# Main.net
KiCad netlist of a schematic drawn in Altium Designer
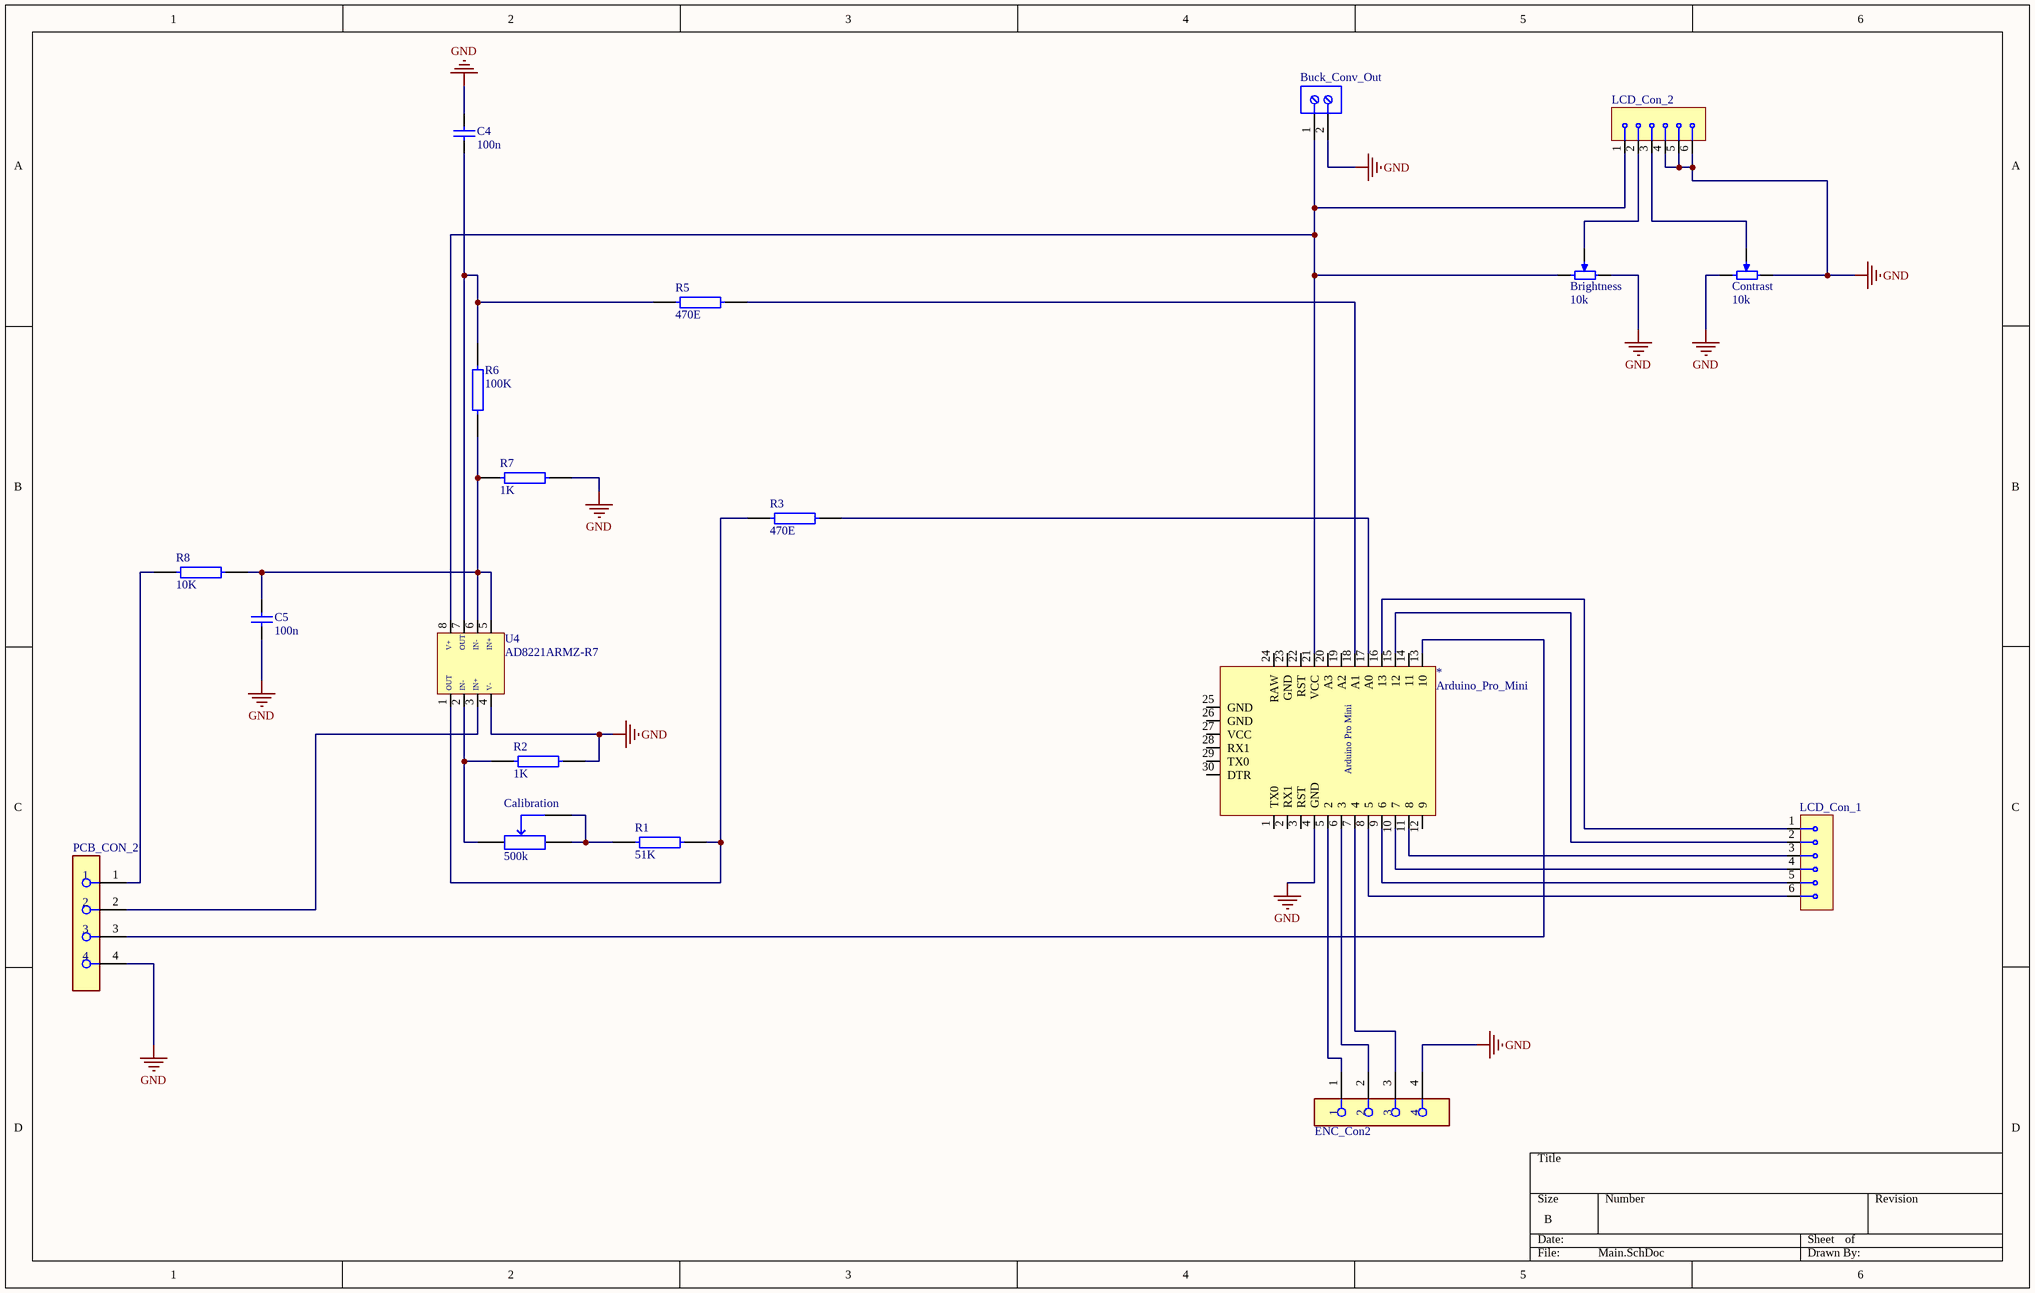
[diagram p0: Main.SchDoc]

(export (version "E")
  (design (tool "Eeschema 10.0.6"))
  (components
    (comp (ref "*")
      (value "Arduino_Pro_Mini")
      (footprint "Arduino_Mini_Pro")
      (libsource (lib "library1") (part "Arduino_Pro_Mini"))
    )
    (comp (ref "Brightness")
      (value "10k")
      (footprint "10k_Trim_Pot")
      (fields (field (name "TOLERANCE") "1%"))
      (libsource (lib "library1") (part "10k_Trim_Pot"))
    )
    (comp (ref "Buck_Conv_Out")
      (value "~")
      (footprint "screw_terminal")
      (fields (field (name "VOLTAGE") "300V"))
      (libsource (lib "library1") (part "Screw_Terminal"))
    )
    (comp (ref "C4")
      (value "100n")
      (footprint "Capacitor_Monolitoc")
      (fields (field (name "TOLERANCE") "10%") (field (name "MANUFACTURER") "Murata"))
      (libsource (lib "library1") (part "Capacitor_Monolitic"))
    )
    (comp (ref "C5")
      (value "100n")
      (footprint "Capacitor_Monolitoc")
      (fields (field (name "TOLERANCE") "10%") (field (name "MANUFACTURER") "Murata"))
      (libsource (lib "library1") (part "Capacitor_Monolitic"))
    )
    (comp (ref "Calibration")
      (value "500k")
      (footprint "500k_Trim_Pot")
      (description "TRIMMER 500K OHM 0.5W PC PIN TOP")
      (fields
        (field (name "MANUFACTURER") "Bourns")
        (field (name "OCTOPART") "https://octopart.com/3296w-1-504lf-bourns-143884")
      )
      (libsource (lib "library1") (part "500k_Trim_Pot"))
    )
    (comp (ref "Contrast")
      (value "10k")
      (footprint "10k_Trim_Pot")
      (fields (field (name "TOLERANCE") "1%"))
      (libsource (lib "library1") (part "10k_Trim_Pot"))
    )
    (comp (ref "ENC_Con2")
      (value "~")
      (footprint "Header-Female-JST_4pin")
      (libsource (lib "") (part "Header-Female-JST_4pin_1"))
    )
    (comp (ref "LCD_Con_1")
      (value "~")
      (footprint "6Pin_Connector")
      (libsource (lib "") (part "6Pin_Connector_1"))
    )
    (comp (ref "LCD_Con_2")
      (value "~")
      (footprint "6Pin_Connector")
      (libsource (lib "library1") (part "6Pin_Connector"))
    )
    (comp (ref "PCB_CON_2")
      (value "~")
      (footprint "Header-Female-JST_4pin")
      (libsource (lib "library1") (part "Header-Female-JST_4pin"))
    )
    (comp (ref "R1")
      (value "51K")
      (footprint "Resistor")
      (fields (field (name "TOLERANCE") "1%"))
      (libsource (lib "library1") (part "Resistor"))
    )
    (comp (ref "R2")
      (value "1K")
      (footprint "Resistor")
      (fields (field (name "TOLERANCE") "1%"))
      (libsource (lib "library1") (part "Resistor"))
    )
    (comp (ref "R3")
      (value "470E")
      (footprint "Resistor")
      (fields (field (name "TOLERANCE") "1%"))
      (libsource (lib "library1") (part "Resistor"))
    )
    (comp (ref "R5")
      (value "470E")
      (footprint "Resistor")
      (fields (field (name "TOLERANCE") "1%"))
      (libsource (lib "library1") (part "Resistor"))
    )
    (comp (ref "R6")
      (value "100K")
      (footprint "Resistor")
      (fields (field (name "TOLERANCE") "1%"))
      (libsource (lib "library1") (part "Resistor"))
    )
    (comp (ref "R7")
      (value "1K")
      (footprint "Resistor")
      (fields (field (name "TOLERANCE") "1%"))
      (libsource (lib "library1") (part "Resistor"))
    )
    (comp (ref "R8")
      (value "10K")
      (footprint "Resistor")
      (fields (field (name "TOLERANCE") "1%"))
      (libsource (lib "library1") (part "Resistor"))
    )
    (comp (ref "U4")
      (value "AD8221ARMZ-R7")
      (footprint "DIP8_AD822")
      (fields (field (name "MANUFACTURER") "Analog Devices"))
      (libsource (lib "library1") (part "OP_AMP_AD822"))
    )
  )
  (nets
    (net (code "1") (name "GND") (class "Default")
      (node (ref "*") (pin "4") (pinfunction "GND_4") (pintype "passive"))
      (node (ref "Brightness") (pin "1") (pinfunction "CCW_1") (pintype "passive"))
      (node (ref "Buck_Conv_Out") (pin "2") (pinfunction "2_2") (pintype "passive"))
      (node (ref "C4") (pin "2") (pinfunction "2_2") (pintype "passive"))
      (node (ref "C5") (pin "1") (pinfunction "1_1") (pintype "passive"))
      (node (ref "Contrast") (pin "1") (pinfunction "CCW_1") (pintype "passive"))
      (node (ref "Contrast") (pin "3") (pinfunction "CW_3") (pintype "passive"))
      (node (ref "ENC_Con2") (pin "4") (pinfunction "4_4") (pintype "passive"))
      (node (ref "LCD_Con_2") (pin "4") (pintype "passive"))
      (node (ref "LCD_Con_2") (pin "5") (pintype "passive"))
      (node (ref "LCD_Con_2") (pin "6") (pintype "passive"))
      (node (ref "PCB_CON_2") (pin "4") (pinfunction "4_4") (pintype "passive"))
      (node (ref "R2") (pin "2") (pinfunction "2_2") (pintype "passive"))
      (node (ref "R7") (pin "2") (pinfunction "2_2") (pintype "passive"))
      (node (ref "U4") (pin "4") (pintype "passive"))
    )
    (net (code "2") (name "Net-(*-2)") (class "Default")
      (node (ref "*") (pin "5") (pinfunction "2_5") (pintype "passive"))
      (node (ref "ENC_Con2") (pin "1") (pinfunction "1_1") (pintype "passive"))
    )
    (net (code "3") (name "Net-(*-3)") (class "Default")
      (node (ref "*") (pin "6") (pinfunction "3_6") (pintype "passive"))
      (node (ref "ENC_Con2") (pin "2") (pinfunction "2_2") (pintype "passive"))
    )
    (net (code "4") (name "Net-(*-4)") (class "Default")
      (node (ref "*") (pin "7") (pinfunction "4_7") (pintype "passive"))
      (node (ref "ENC_Con2") (pin "3") (pinfunction "3_3") (pintype "passive"))
    )
    (net (code "5") (name "Net-(*-5)") (class "Default")
      (node (ref "*") (pin "8") (pinfunction "5_8") (pintype "passive"))
      (node (ref "LCD_Con_1") (pin "6") (pintype "passive"))
    )
    (net (code "6") (name "Net-(*-6)") (class "Default")
      (node (ref "*") (pin "9") (pinfunction "6_9") (pintype "passive"))
      (node (ref "LCD_Con_1") (pin "5") (pintype "passive"))
    )
    (net (code "7") (name "Net-(*-7)") (class "Default")
      (node (ref "*") (pin "10") (pinfunction "7_10") (pintype "passive"))
      (node (ref "LCD_Con_1") (pin "4") (pintype "passive"))
    )
    (net (code "8") (name "Net-(*-8)") (class "Default")
      (node (ref "*") (pin "11") (pinfunction "8_11") (pintype "passive"))
      (node (ref "LCD_Con_1") (pin "3") (pintype "passive"))
    )
    (net (code "9") (name "Net-(*-10)") (class "Default")
      (node (ref "*") (pin "13") (pinfunction "10_13") (pintype "passive"))
      (node (ref "PCB_CON_2") (pin "3") (pinfunction "3_3") (pintype "passive"))
    )
    (net (code "10") (name "Net-(*-12)") (class "Default")
      (node (ref "*") (pin "15") (pinfunction "12_15") (pintype "passive"))
      (node (ref "LCD_Con_1") (pin "2") (pinfunction "2_2") (pintype "passive"))
    )
    (net (code "11") (name "Net-(*-13)") (class "Default")
      (node (ref "*") (pin "16") (pinfunction "13_16") (pintype "passive"))
      (node (ref "LCD_Con_1") (pin "1") (pinfunction "1_1") (pintype "passive"))
    )
    (net (code "12") (name "Net-(*-A0)") (class "Default")
      (node (ref "*") (pin "17") (pinfunction "A0_17") (pintype "passive"))
      (node (ref "R3") (pin "2") (pinfunction "2_2") (pintype "passive"))
    )
    (net (code "13") (name "Net-(*-A1)") (class "Default")
      (node (ref "*") (pin "18") (pinfunction "A1_18") (pintype "passive"))
      (node (ref "R5") (pin "2") (pinfunction "2_2") (pintype "passive"))
    )
    (net (code "14") (name "Net-(Brightness-CW)") (class "Default")
      (node (ref "*") (pin "21") (pinfunction "VCC_21") (pintype "passive"))
      (node (ref "Brightness") (pin "3") (pinfunction "CW_3") (pintype "passive"))
      (node (ref "Buck_Conv_Out") (pin "1") (pinfunction "1_1") (pintype "passive"))
      (node (ref "LCD_Con_2") (pin "1") (pinfunction "1_1") (pintype "passive"))
      (node (ref "U4") (pin "8") (pintype "passive"))
    )
    (net (code "15") (name "Net-(Brightness-S)") (class "Default")
      (node (ref "Brightness") (pin "2") (pinfunction "S_2") (pintype "passive"))
      (node (ref "LCD_Con_2") (pin "2") (pinfunction "2_2") (pintype "passive"))
    )
    (net (code "16") (name "Net-(C4-Pad1)") (class "Default")
      (node (ref "C4") (pin "1") (pinfunction "1_1") (pintype "passive"))
      (node (ref "R5") (pin "1") (pinfunction "1_1") (pintype "passive"))
      (node (ref "R6") (pin "2") (pinfunction "2_2") (pintype "passive"))
      (node (ref "U4") (pin "7") (pintype "passive"))
    )
    (net (code "17") (name "Net-(C5-Pad2)") (class "Default")
      (node (ref "C5") (pin "2") (pinfunction "2_2") (pintype "passive"))
      (node (ref "R6") (pin "1") (pinfunction "1_1") (pintype "passive"))
      (node (ref "R7") (pin "1") (pinfunction "1_1") (pintype "passive"))
      (node (ref "R8") (pin "2") (pinfunction "2_2") (pintype "passive"))
      (node (ref "U4") (pin "5") (pintype "passive"))
      (node (ref "U4") (pin "6") (pintype "passive"))
    )
    (net (code "18") (name "Net-(Calibration-CCW)") (class "Default")
      (node (ref "Calibration") (pin "1") (pinfunction "CCW_1") (pintype "passive"))
      (node (ref "Calibration") (pin "2") (pinfunction "WIPER_2") (pintype "passive"))
      (node (ref "R1") (pin "1") (pinfunction "1_1") (pintype "passive"))
    )
    (net (code "19") (name "Net-(Calibration-CW)") (class "Default")
      (node (ref "Calibration") (pin "3") (pinfunction "CW_3") (pintype "passive"))
      (node (ref "R2") (pin "1") (pinfunction "1_1") (pintype "passive"))
      (node (ref "U4") (pin "2") (pintype "passive"))
    )
    (net (code "20") (name "Net-(Contrast-S)") (class "Default")
      (node (ref "Contrast") (pin "2") (pinfunction "S_2") (pintype "passive"))
      (node (ref "LCD_Con_2") (pin "3") (pintype "passive"))
    )
    (net (code "21") (name "Net-(PCB_CON_2-Pad1)") (class "Default")
      (node (ref "PCB_CON_2") (pin "1") (pinfunction "1_1") (pintype "passive"))
      (node (ref "R8") (pin "1") (pinfunction "1_1") (pintype "passive"))
    )
    (net (code "22") (name "Net-(PCB_CON_2-Pad2)") (class "Default")
      (node (ref "PCB_CON_2") (pin "2") (pinfunction "2_2") (pintype "passive"))
      (node (ref "U4") (pin "3") (pintype "passive"))
    )
    (net (code "23") (name "Net-(R1-Pad2)") (class "Default")
      (node (ref "R1") (pin "2") (pinfunction "2_2") (pintype "passive"))
      (node (ref "R3") (pin "1") (pinfunction "1_1") (pintype "passive"))
      (node (ref "U4") (pin "1") (pintype "passive"))
    )
    (net (code "24") (name "unconnected-(*-9-Pad12)") (class "Default")
      (node (ref "*") (pin "12") (pinfunction "9_12") (pintype "passive"))
    )
    (net (code "25") (name "unconnected-(*-11-Pad14)") (class "Default")
      (node (ref "*") (pin "14") (pinfunction "11_14") (pintype "passive"))
    )
    (net (code "26") (name "unconnected-(*-A2-Pad19)") (class "Default")
      (node (ref "*") (pin "19") (pinfunction "A2_19") (pintype "passive"))
    )
    (net (code "27") (name "unconnected-(*-A3-Pad20)") (class "Default")
      (node (ref "*") (pin "20") (pinfunction "A3_20") (pintype "passive"))
    )
    (net (code "28") (name "unconnected-(*-DTR-Pad30)") (class "Default")
      (node (ref "*") (pin "30") (pinfunction "DTR_30") (pintype "passive"))
    )
    (net (code "29") (name "unconnected-(*-GND-Pad23)") (class "Default")
      (node (ref "*") (pin "23") (pinfunction "GND_23") (pintype "passive"))
    )
    (net (code "30") (name "unconnected-(*-GND-Pad25)") (class "Default")
      (node (ref "*") (pin "25") (pinfunction "GND_25") (pintype "passive"))
    )
    (net (code "31") (name "unconnected-(*-GND-Pad26)") (class "Default")
      (node (ref "*") (pin "26") (pinfunction "GND_26") (pintype "passive"))
    )
    (net (code "32") (name "unconnected-(*-RAW-Pad24)") (class "Default")
      (node (ref "*") (pin "24") (pinfunction "RAW_24") (pintype "passive"))
    )
    (net (code "33") (name "unconnected-(*-RST-Pad3)") (class "Default")
      (node (ref "*") (pin "3") (pinfunction "RST_3") (pintype "passive"))
    )
    (net (code "34") (name "unconnected-(*-RST-Pad22)") (class "Default")
      (node (ref "*") (pin "22") (pinfunction "RST_22") (pintype "passive"))
    )
    (net (code "35") (name "unconnected-(*-RX1-Pad2)") (class "Default")
      (node (ref "*") (pin "2") (pinfunction "RX1_2") (pintype "passive"))
    )
    (net (code "36") (name "unconnected-(*-RX1-Pad28)") (class "Default")
      (node (ref "*") (pin "28") (pinfunction "RX1_28") (pintype "passive"))
    )
    (net (code "37") (name "unconnected-(*-TX0-Pad1)") (class "Default")
      (node (ref "*") (pin "1") (pinfunction "TX0_1") (pintype "passive"))
    )
    (net (code "38") (name "unconnected-(*-TX0-Pad29)") (class "Default")
      (node (ref "*") (pin "29") (pinfunction "TX0_29") (pintype "passive"))
    )
    (net (code "39") (name "unconnected-(*-VCC-Pad27)") (class "Default")
      (node (ref "*") (pin "27") (pinfunction "VCC_27") (pintype "passive"))
    )
  )
)
